# AIR.net
KiCad netlist of a schematic drawn in EAGLE
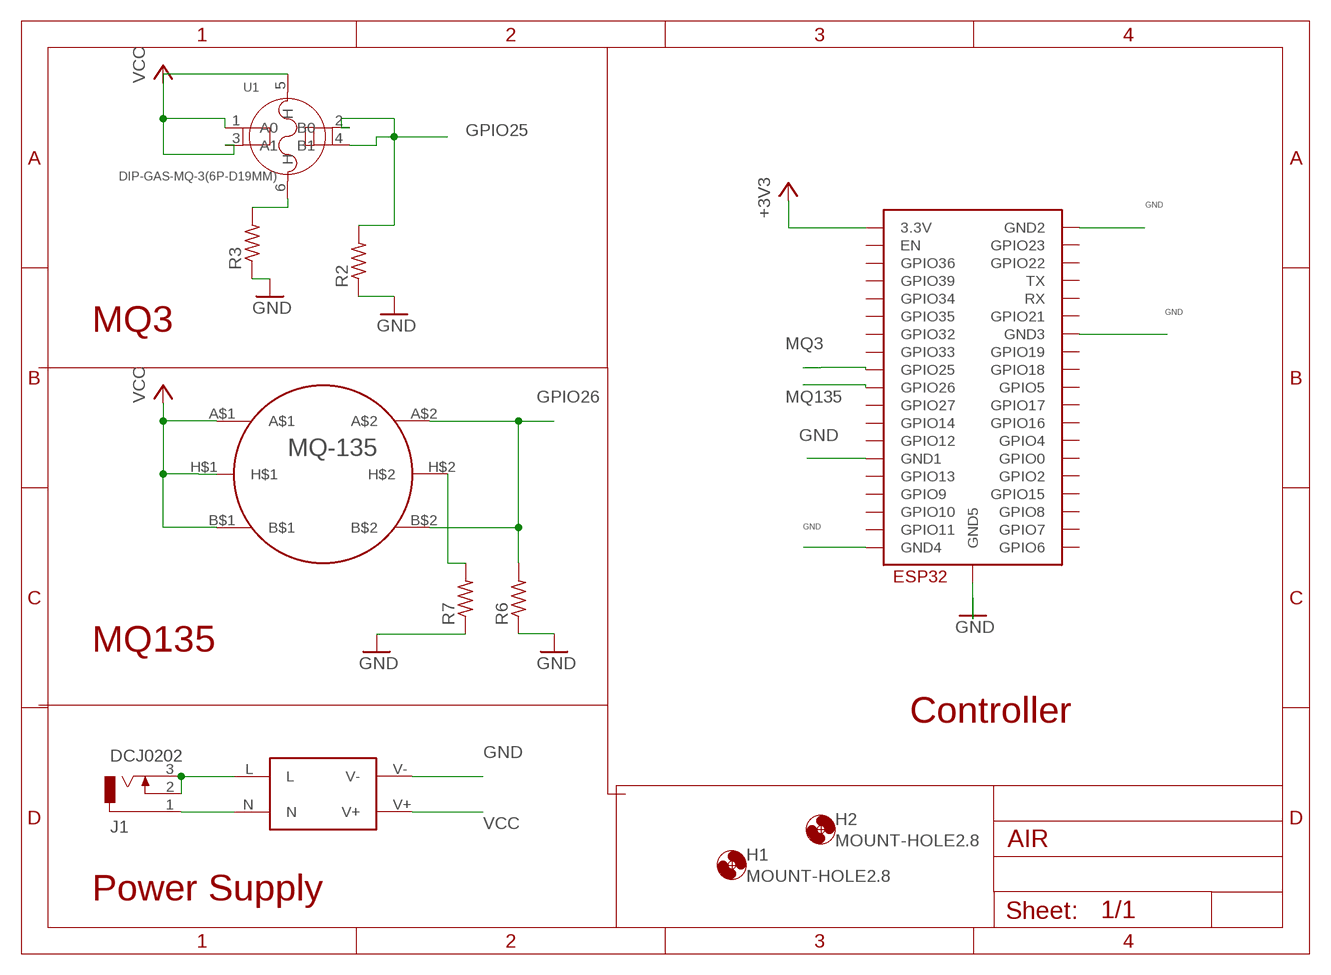
[diagram p0: schematic, sheet 1]

(export (version "E")
  (design (tool "Eeschema 10.0.6"))
  (components
    (comp (ref "H1")
      (value "MOUNT-HOLE2.8")
      (footprint "eagle-import:2,8")
      (libsource (lib "eagle-import") (part "MOUNT-HOLE2.8"))
    )
    (comp (ref "H2")
      (value "MOUNT-HOLE2.8")
      (footprint "eagle-import:2,8")
      (libsource (lib "eagle-import") (part "MOUNT-HOLE2.8"))
    )
    (comp (ref "J1")
      (value "DCJ0202")
      (footprint "eagle-import:DCJ0202")
      (libsource (lib "eagle-import") (part "DCJ0202"))
    )
    (comp (ref "R2")
      (value "R-US_0204/7")
      (footprint "eagle-import:0204_7")
      (libsource (lib "eagle-import") (part "R-US_0204/7"))
    )
    (comp (ref "R3")
      (value "R-US_0204/7")
      (footprint "eagle-import:0204_7")
      (libsource (lib "eagle-import") (part "R-US_0204/7"))
    )
    (comp (ref "R6")
      (value "R-US_0204/7")
      (footprint "eagle-import:0204_7")
      (libsource (lib "eagle-import") (part "R-US_0204/7"))
    )
    (comp (ref "R7")
      (value "R-US_0204/7")
      (footprint "eagle-import:0204_7")
      (libsource (lib "eagle-import") (part "R-US_0204/7"))
    )
    (comp (ref "U$1")
      (value "ESP32-WROOM")
      (footprint "eagle-import:ESP32-WROOM")
      (libsource (lib "eagle-import") (part "ESP32-WROOM"))
    )
    (comp (ref "U$2")
      (value "HLK-PM01")
      (footprint "eagle-import:HLK-PM01-PAK")
      (fields (field (name "MF") "Hi-link") (field (name "MP") "hlk-pm01"))
      (libsource (lib "eagle-import") (part "HLK-PM01"))
    )
    (comp (ref "U$3")
      (value "MQ_135_A")
      (footprint "eagle-import:MQ-135")
      (libsource (lib "eagle-import") (part "MQ_135_A"))
    )
    (comp (ref "U1")
      (value "DIP-GAS-MQ-3(6P-D19MM)")
      (footprint "eagle-import:SNR6-D19.0MM")
      (fields (field (name "MF") "Samsung Electro-Mechanics") (field (name "MP") "MQ3"))
      (libsource (lib "eagle-import") (part "DIP-GAS-MQ-3(6P-D19MM)"))
    )
  )
  (nets
    (net (code "1") (name "+3V3") (class "Default")
      (node (ref "U$1") (pin "3V3") (pinfunction "3.3V_3V3") (pintype "bidirectional"))
    )
    (net (code "2") (name "/GPIO25") (class "Default")
      (node (ref "R2") (pin "2") (pinfunction "2_2") (pintype "passive"))
      (node (ref "U1") (pin "2") (pinfunction "B0_2") (pintype "bidirectional"))
      (node (ref "U1") (pin "4") (pinfunction "B1_4") (pintype "bidirectional"))
    )
    (net (code "3") (name "/GPIO26") (class "Default")
      (node (ref "R6") (pin "2") (pinfunction "2_2") (pintype "passive"))
      (node (ref "U$3") (pin "A$2") (pinfunction "A$2_A$2") (pintype "bidirectional"))
      (node (ref "U$3") (pin "B$2") (pinfunction "B$2_B$2") (pintype "bidirectional"))
    )
    (net (code "4") (name "/MQ3") (class "Default")
      (node (ref "U$1") (pin "IO25") (pinfunction "GPIO25_IO25") (pintype "bidirectional"))
    )
    (net (code "5") (name "/MQ135") (class "Default")
      (node (ref "U$1") (pin "IO26") (pinfunction "GPIO26_IO26") (pintype "bidirectional"))
    )
    (net (code "6") (name "GND") (class "Default")
      (node (ref "R2") (pin "1") (pinfunction "1_1") (pintype "passive"))
      (node (ref "R3") (pin "1") (pinfunction "1_1") (pintype "passive"))
      (node (ref "R6") (pin "1") (pinfunction "1_1") (pintype "passive"))
      (node (ref "R7") (pin "1") (pinfunction "1_1") (pintype "passive"))
      (node (ref "U$1") (pin "GND1") (pinfunction "GND1_GND1") (pintype "bidirectional"))
      (node (ref "U$1") (pin "GND2") (pinfunction "GND2_GND2") (pintype "bidirectional"))
      (node (ref "U$1") (pin "GND3") (pinfunction "GND3_GND3") (pintype "bidirectional"))
      (node (ref "U$1") (pin "GND4") (pinfunction "GND4_GND4") (pintype "bidirectional"))
      (node (ref "U$1") (pin "GND5") (pinfunction "GND5_GND5") (pintype "bidirectional"))
      (node (ref "U$2") (pin "V-") (pinfunction "V-_V-") (pintype "bidirectional"))
    )
    (net (code "7") (name "Net-(J1-Pad1)") (class "Default")
      (node (ref "J1") (pin "1") (pinfunction "1_1") (pintype "passive"))
      (node (ref "U$2") (pin "N") (pinfunction "N_N") (pintype "bidirectional"))
    )
    (net (code "8") (name "Net-(J1-Pad2)") (class "Default")
      (node (ref "J1") (pin "2") (pinfunction "2_2") (pintype "passive"))
      (node (ref "J1") (pin "3") (pinfunction "3_3") (pintype "passive"))
      (node (ref "U$2") (pin "L") (pinfunction "L_L") (pintype "bidirectional"))
    )
    (net (code "9") (name "Net-(R3-Pad2)") (class "Default")
      (node (ref "R3") (pin "2") (pinfunction "2_2") (pintype "passive"))
      (node (ref "U1") (pin "6") (pinfunction "H_6") (pintype "bidirectional"))
    )
    (net (code "10") (name "Net-(R7-Pad2)") (class "Default")
      (node (ref "R7") (pin "2") (pinfunction "2_2") (pintype "passive"))
      (node (ref "U$3") (pin "H$2") (pinfunction "H$2_H$2") (pintype "bidirectional"))
    )
    (net (code "11") (name "VCC") (class "Default")
      (node (ref "U$2") (pin "V+") (pinfunction "V+_V+") (pintype "bidirectional"))
      (node (ref "U$3") (pin "A$1") (pinfunction "A$1_A$1") (pintype "bidirectional"))
      (node (ref "U$3") (pin "B$1") (pinfunction "B$1_B$1") (pintype "bidirectional"))
      (node (ref "U$3") (pin "H$1") (pinfunction "H$1_H$1") (pintype "bidirectional"))
      (node (ref "U1") (pin "1") (pinfunction "A0_1") (pintype "bidirectional"))
      (node (ref "U1") (pin "3") (pinfunction "A1_3") (pintype "bidirectional"))
      (node (ref "U1") (pin "5") (pinfunction "H_5") (pintype "bidirectional"))
    )
    (net (code "12") (name "unconnected-(U$1-GPIO0-PadIO0)") (class "Default")
      (node (ref "U$1") (pin "IO0") (pinfunction "GPIO0_IO0") (pintype "bidirectional"))
    )
    (net (code "13") (name "unconnected-(U$1-GPIO2-PadIO2)") (class "Default")
      (node (ref "U$1") (pin "IO2") (pinfunction "GPIO2_IO2") (pintype "bidirectional"))
    )
    (net (code "14") (name "unconnected-(U$1-GPIO4-PadIO4)") (class "Default")
      (node (ref "U$1") (pin "IO4") (pinfunction "GPIO4_IO4") (pintype "bidirectional"))
    )
    (net (code "15") (name "unconnected-(U$1-GPIO5-PadIO5)") (class "Default")
      (node (ref "U$1") (pin "IO5") (pinfunction "GPIO5_IO5") (pintype "bidirectional"))
    )
    (net (code "16") (name "unconnected-(U$1-GPIO6-PadCLK)") (class "Default")
      (node (ref "U$1") (pin "CLK") (pinfunction "GPIO6_CLK") (pintype "bidirectional"))
    )
    (net (code "17") (name "unconnected-(U$1-GPIO7-PadSD0)") (class "Default")
      (node (ref "U$1") (pin "SD0") (pinfunction "GPIO7_SD0") (pintype "bidirectional"))
    )
    (net (code "18") (name "unconnected-(U$1-GPIO8-PadSD1)") (class "Default")
      (node (ref "U$1") (pin "SD1") (pinfunction "GPIO8_SD1") (pintype "bidirectional"))
    )
    (net (code "19") (name "unconnected-(U$1-GPIO9-PadSD2)") (class "Default")
      (node (ref "U$1") (pin "SD2") (pinfunction "GPIO9_SD2") (pintype "bidirectional"))
    )
    (net (code "20") (name "unconnected-(U$1-GPIO10-PadSD3)") (class "Default")
      (node (ref "U$1") (pin "SD3") (pinfunction "GPIO10_SD3") (pintype "bidirectional"))
    )
    (net (code "21") (name "unconnected-(U$1-GPIO11-PadCMD)") (class "Default")
      (node (ref "U$1") (pin "CMD") (pinfunction "GPIO11_CMD") (pintype "bidirectional"))
    )
    (net (code "22") (name "unconnected-(U$1-GPIO12-PadIO12)") (class "Default")
      (node (ref "U$1") (pin "IO12") (pinfunction "GPIO12_IO12") (pintype "bidirectional"))
    )
    (net (code "23") (name "unconnected-(U$1-GPIO13-PadIO13)") (class "Default")
      (node (ref "U$1") (pin "IO13") (pinfunction "GPIO13_IO13") (pintype "bidirectional"))
    )
    (net (code "24") (name "unconnected-(U$1-GPIO14-PadIO14)") (class "Default")
      (node (ref "U$1") (pin "IO14") (pinfunction "GPIO14_IO14") (pintype "bidirectional"))
    )
    (net (code "25") (name "unconnected-(U$1-GPIO15-PadIO15)") (class "Default")
      (node (ref "U$1") (pin "IO15") (pinfunction "GPIO15_IO15") (pintype "bidirectional"))
    )
    (net (code "26") (name "unconnected-(U$1-GPIO16-PadIO16)") (class "Default")
      (node (ref "U$1") (pin "IO16") (pinfunction "GPIO16_IO16") (pintype "bidirectional"))
    )
    (net (code "27") (name "unconnected-(U$1-GPIO17-PadIO17)") (class "Default")
      (node (ref "U$1") (pin "IO17") (pinfunction "GPIO17_IO17") (pintype "bidirectional"))
    )
    (net (code "28") (name "unconnected-(U$1-GPIO18-PadIO18)") (class "Default")
      (node (ref "U$1") (pin "IO18") (pinfunction "GPIO18_IO18") (pintype "bidirectional"))
    )
    (net (code "29") (name "unconnected-(U$1-GPIO19-PadIO19)") (class "Default")
      (node (ref "U$1") (pin "IO19") (pinfunction "GPIO19_IO19") (pintype "bidirectional"))
    )
    (net (code "30") (name "unconnected-(U$1-GPIO21-PadIO21)") (class "Default")
      (node (ref "U$1") (pin "IO21") (pinfunction "GPIO21_IO21") (pintype "bidirectional"))
    )
    (net (code "31") (name "unconnected-(U$1-GPIO22-PadIO22)") (class "Default")
      (node (ref "U$1") (pin "IO22") (pinfunction "GPIO22_IO22") (pintype "bidirectional"))
    )
    (net (code "32") (name "unconnected-(U$1-GPIO23-PadIO23)") (class "Default")
      (node (ref "U$1") (pin "IO23") (pinfunction "GPIO23_IO23") (pintype "bidirectional"))
    )
    (net (code "33") (name "unconnected-(U$1-GPIO27-PadIO27)") (class "Default")
      (node (ref "U$1") (pin "IO27") (pinfunction "GPIO27_IO27") (pintype "bidirectional"))
    )
    (net (code "34") (name "unconnected-(U$1-GPIO32-PadIO32)") (class "Default")
      (node (ref "U$1") (pin "IO32") (pinfunction "GPIO32_IO32") (pintype "bidirectional"))
    )
    (net (code "35") (name "unconnected-(U$1-GPIO33-PadIO33)") (class "Default")
      (node (ref "U$1") (pin "IO33") (pinfunction "GPIO33_IO33") (pintype "bidirectional"))
    )
    (net (code "36") (name "unconnected-(U$1-GPIO34-PadIO34)") (class "Default")
      (node (ref "U$1") (pin "IO34") (pinfunction "GPIO34_IO34") (pintype "bidirectional"))
    )
    (net (code "37") (name "unconnected-(U$1-GPIO35-PadIO35)") (class "Default")
      (node (ref "U$1") (pin "IO35") (pinfunction "GPIO35_IO35") (pintype "bidirectional"))
    )
    (net (code "38") (name "unconnected-(U$1-GPIO36-PadSENSOR_VP)") (class "Default")
      (node (ref "U$1") (pin "SENSOR_VP") (pinfunction "GPIO36_SENSOR_VP") (pintype "bidirectional"))
    )
    (net (code "39") (name "unconnected-(U$1-GPIO39-PadSENSOR_VN)") (class "Default")
      (node (ref "U$1") (pin "SENSOR_VN") (pinfunction "GPIO39_SENSOR_VN") (pintype "bidirectional"))
    )
    (net (code "40") (name "unconnected-(U$1-PadEN)") (class "Default")
      (node (ref "U$1") (pin "EN") (pinfunction "EN_EN") (pintype "bidirectional"))
    )
    (net (code "41") (name "unconnected-(U$1-PadRX)") (class "Default")
      (node (ref "U$1") (pin "RX") (pinfunction "RX_RX") (pintype "bidirectional"))
    )
    (net (code "42") (name "unconnected-(U$1-PadTX)") (class "Default")
      (node (ref "U$1") (pin "TX") (pinfunction "TX_TX") (pintype "bidirectional"))
    )
  )
)
